# remote_mini.net
KiCad netlist of a schematic drawn in EAGLE
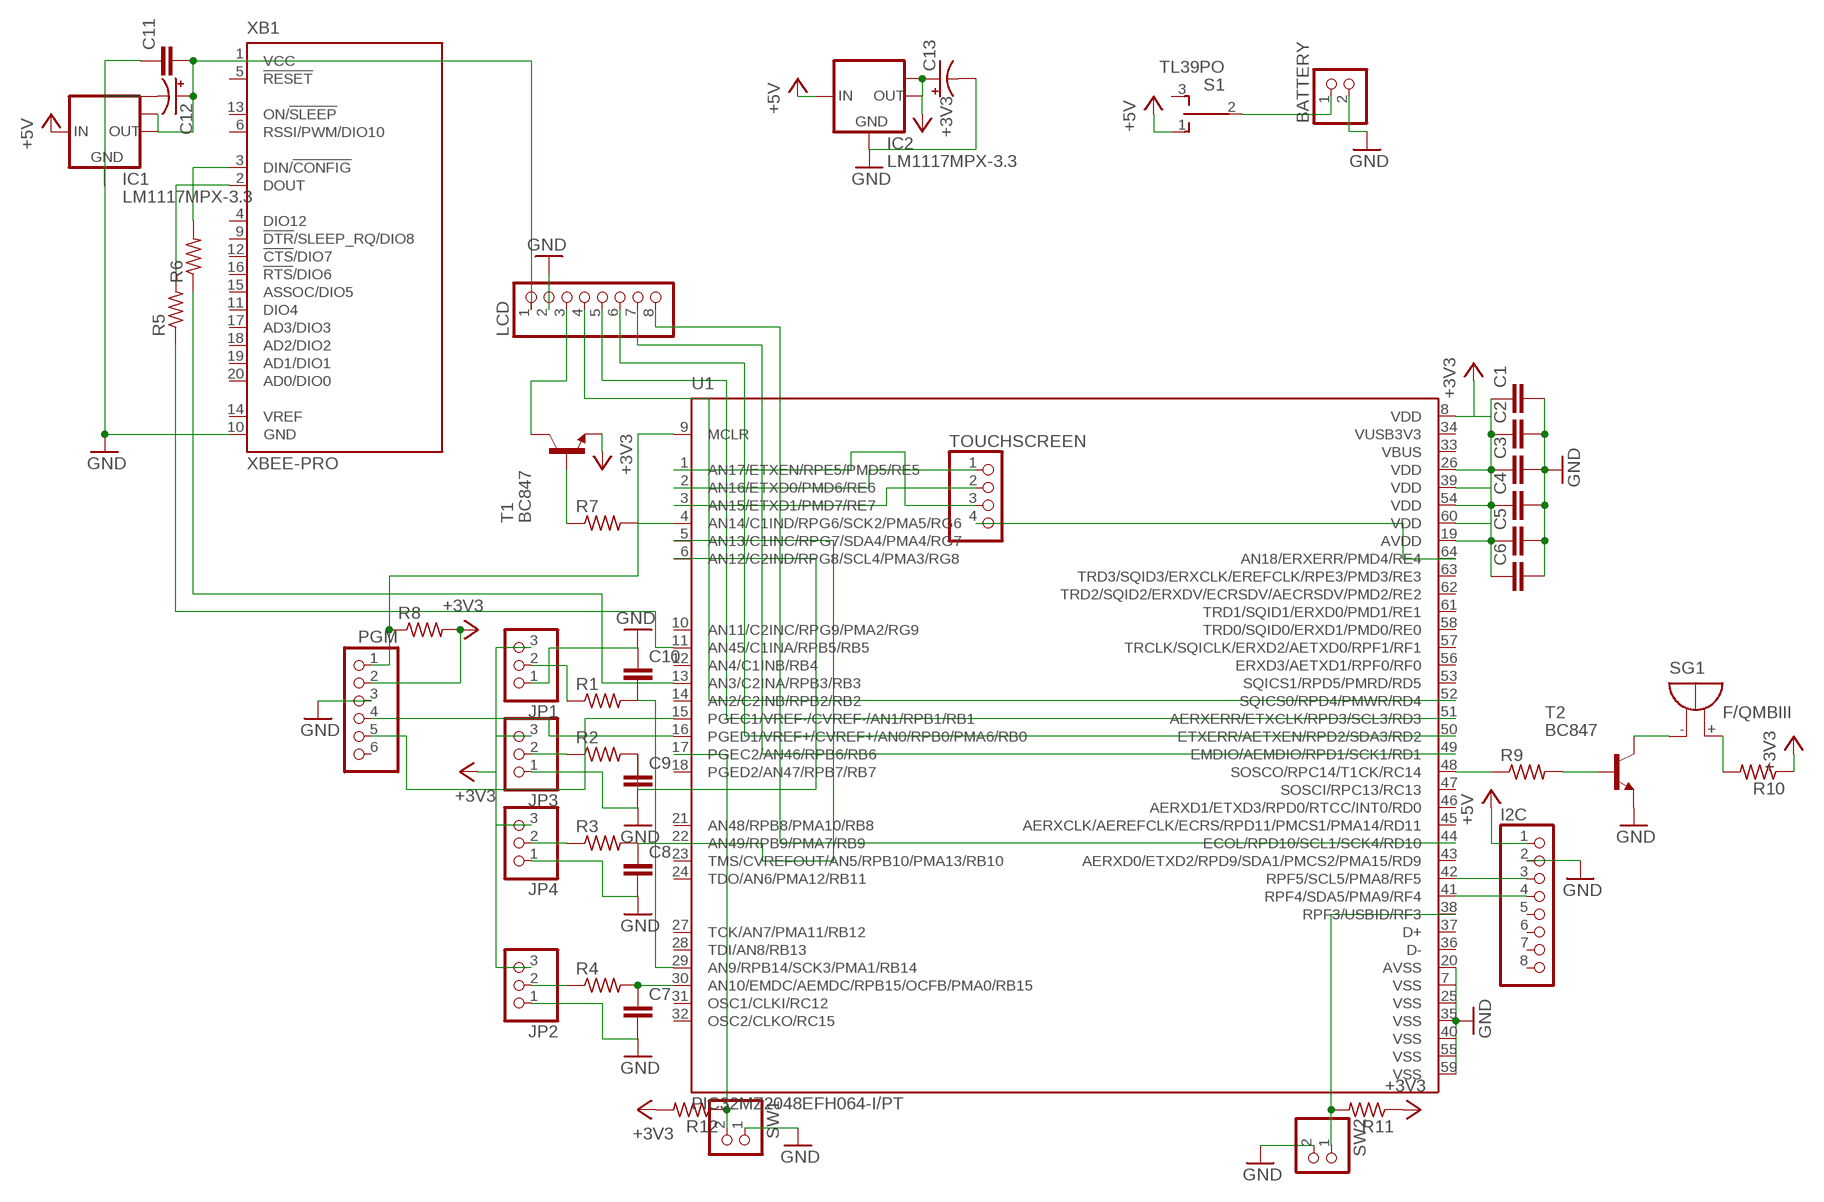
[diagram p0: schematic, sheet 1]

(export (version "E")
  (design (tool "Eeschema 10.0.6"))
  (components
    (comp (ref "BATTERY")
      (value "PINHD-1X2")
      (footprint "eagle-import:1X02")
      (libsource (lib "eagle-import") (part "PINHD-1X2"))
    )
    (comp (ref "C1")
      (value "C-EUC0603")
      (footprint "eagle-import:C0603")
      (libsource (lib "eagle-import") (part "C-EUC0603"))
    )
    (comp (ref "C2")
      (value "C-EUC0603")
      (footprint "eagle-import:C0603")
      (libsource (lib "eagle-import") (part "C-EUC0603"))
    )
    (comp (ref "C3")
      (value "C-EUC0603")
      (footprint "eagle-import:C0603")
      (libsource (lib "eagle-import") (part "C-EUC0603"))
    )
    (comp (ref "C4")
      (value "C-EUC0603")
      (footprint "eagle-import:C0603")
      (libsource (lib "eagle-import") (part "C-EUC0603"))
    )
    (comp (ref "C5")
      (value "C-EUC0603")
      (footprint "eagle-import:C0603")
      (libsource (lib "eagle-import") (part "C-EUC0603"))
    )
    (comp (ref "C6")
      (value "C-EUC0603")
      (footprint "eagle-import:C0603")
      (libsource (lib "eagle-import") (part "C-EUC0603"))
    )
    (comp (ref "C7")
      (value "C-EUC0805")
      (footprint "eagle-import:C0805")
      (libsource (lib "eagle-import") (part "C-EUC0805"))
    )
    (comp (ref "C8")
      (value "C-EUC0805")
      (footprint "eagle-import:C0805")
      (libsource (lib "eagle-import") (part "C-EUC0805"))
    )
    (comp (ref "C9")
      (value "C-EUC0805")
      (footprint "eagle-import:C0805")
      (libsource (lib "eagle-import") (part "C-EUC0805"))
    )
    (comp (ref "C10")
      (value "C-EUC0805")
      (footprint "eagle-import:C0805")
      (libsource (lib "eagle-import") (part "C-EUC0805"))
    )
    (comp (ref "C11")
      (value "C-EUC0603")
      (footprint "eagle-import:C0603")
      (libsource (lib "eagle-import") (part "C-EUC0603"))
    )
    (comp (ref "C12")
      (value "CPOL-USCT7343")
      (footprint "eagle-import:CT7343")
      (libsource (lib "eagle-import") (part "CPOL-USCT7343"))
    )
    (comp (ref "C13")
      (value "CPOL-USCT7343")
      (footprint "eagle-import:CT7343")
      (libsource (lib "eagle-import") (part "CPOL-USCT7343"))
    )
    (comp (ref "I2C")
      (value "PINHD-1X8")
      (footprint "eagle-import:1X08")
      (libsource (lib "eagle-import") (part "PINHD-1X8"))
    )
    (comp (ref "IC1")
      (value "LM1117MPX-3.3")
      (footprint "eagle-import:SOT223")
      (libsource (lib "eagle-import") (part "LM1117MPX-3.3"))
    )
    (comp (ref "IC2")
      (value "LM1117MPX-3.3")
      (footprint "eagle-import:SOT223")
      (libsource (lib "eagle-import") (part "LM1117MPX-3.3"))
    )
    (comp (ref "JP1")
      (value "PINHD-1X3")
      (footprint "eagle-import:1X03")
      (libsource (lib "eagle-import") (part "PINHD-1X3"))
    )
    (comp (ref "JP2")
      (value "PINHD-1X3")
      (footprint "eagle-import:1X03")
      (libsource (lib "eagle-import") (part "PINHD-1X3"))
    )
    (comp (ref "JP3")
      (value "PINHD-1X3")
      (footprint "eagle-import:1X03")
      (libsource (lib "eagle-import") (part "PINHD-1X3"))
    )
    (comp (ref "JP4")
      (value "PINHD-1X3")
      (footprint "eagle-import:1X03")
      (libsource (lib "eagle-import") (part "PINHD-1X3"))
    )
    (comp (ref "LCD")
      (value "PINHD-1X8")
      (footprint "eagle-import:1X08")
      (libsource (lib "eagle-import") (part "PINHD-1X8"))
    )
    (comp (ref "PGM")
      (value "PINHD-1X6")
      (footprint "eagle-import:1X06")
      (libsource (lib "eagle-import") (part "PINHD-1X6"))
    )
    (comp (ref "R1")
      (value "R-US_R0603")
      (footprint "eagle-import:R0603")
      (libsource (lib "eagle-import") (part "R-US_R0603"))
    )
    (comp (ref "R2")
      (value "R-US_R0603")
      (footprint "eagle-import:R0603")
      (libsource (lib "eagle-import") (part "R-US_R0603"))
    )
    (comp (ref "R3")
      (value "R-US_R0603")
      (footprint "eagle-import:R0603")
      (libsource (lib "eagle-import") (part "R-US_R0603"))
    )
    (comp (ref "R4")
      (value "R-US_R0603")
      (footprint "eagle-import:R0603")
      (libsource (lib "eagle-import") (part "R-US_R0603"))
    )
    (comp (ref "R5")
      (value "R-US_R0603")
      (footprint "eagle-import:R0603")
      (libsource (lib "eagle-import") (part "R-US_R0603"))
    )
    (comp (ref "R6")
      (value "R-US_R0603")
      (footprint "eagle-import:R0603")
      (libsource (lib "eagle-import") (part "R-US_R0603"))
    )
    (comp (ref "R7")
      (value "R-US_R0603")
      (footprint "eagle-import:R0603")
      (libsource (lib "eagle-import") (part "R-US_R0603"))
    )
    (comp (ref "R8")
      (value "R-US_R0603")
      (footprint "eagle-import:R0603")
      (libsource (lib "eagle-import") (part "R-US_R0603"))
    )
    (comp (ref "R9")
      (value "R-US_R0603")
      (footprint "eagle-import:R0603")
      (libsource (lib "eagle-import") (part "R-US_R0603"))
    )
    (comp (ref "R10")
      (value "R-US_R0603")
      (footprint "eagle-import:R0603")
      (libsource (lib "eagle-import") (part "R-US_R0603"))
    )
    (comp (ref "R11")
      (value "R-US_R0603")
      (footprint "eagle-import:R0603")
      (libsource (lib "eagle-import") (part "R-US_R0603"))
    )
    (comp (ref "R12")
      (value "R-US_R0603")
      (footprint "eagle-import:R0603")
      (libsource (lib "eagle-import") (part "R-US_R0603"))
    )
    (comp (ref "S1")
      (value "TL39PO")
      (footprint "eagle-import:TL3XPO")
      (libsource (lib "eagle-import") (part "TL39PO"))
    )
    (comp (ref "SG1")
      (value "F/QMBIII")
      (footprint "eagle-import:F_QMBIII")
      (libsource (lib "eagle-import") (part "F/QMBIII"))
    )
    (comp (ref "SW1")
      (value "PINHD-1X2")
      (footprint "eagle-import:1X02")
      (libsource (lib "eagle-import") (part "PINHD-1X2"))
    )
    (comp (ref "SW2")
      (value "PINHD-1X2")
      (footprint "eagle-import:1X02")
      (libsource (lib "eagle-import") (part "PINHD-1X2"))
    )
    (comp (ref "T1")
      (value "BC847")
      (footprint "eagle-import:SOT23")
      (libsource (lib "eagle-import") (part "BC847"))
    )
    (comp (ref "T2")
      (value "BC847")
      (footprint "eagle-import:SOT23")
      (libsource (lib "eagle-import") (part "BC847"))
    )
    (comp (ref "TOUCHSCREEN")
      (value "PINHD-1X4")
      (footprint "eagle-import:1X04")
      (libsource (lib "eagle-import") (part "PINHD-1X4"))
    )
    (comp (ref "U1")
      (value "PIC32MZ2048EFH064-I/PT")
      (footprint "eagle-import:QFP50P1200X1200X120-64N")
      (fields (field (name "MF") "Microchip"))
      (libsource (lib "eagle-import") (part "PIC32MZ2048EFH064-I/PT"))
    )
    (comp (ref "XB1")
      (value "XBEE-PRO")
      (footprint "eagle-import:XBEE-PRO")
      (fields (field (name "MPN") "XBP24-AWI-001"))
      (libsource (lib "eagle-import") (part "XBEE-PRO"))
    )
  )
  (nets
    (net (code "1") (name "+3V3") (class "Default")
      (node (ref "C1") (pin "1") (pinfunction "1_1") (pintype "passive"))
      (node (ref "C13") (pin "+") (pinfunction "+_+") (pintype "passive"))
      (node (ref "C2") (pin "1") (pinfunction "1_1") (pintype "passive"))
      (node (ref "C3") (pin "1") (pinfunction "1_1") (pintype "passive"))
      (node (ref "C4") (pin "1") (pinfunction "1_1") (pintype "passive"))
      (node (ref "C5") (pin "1") (pinfunction "1_1") (pintype "passive"))
      (node (ref "C6") (pin "1") (pinfunction "1_1") (pintype "passive"))
      (node (ref "IC2") (pin "2") (pinfunction "OUT_2") (pintype "passive"))
      (node (ref "IC2") (pin "TAB") (pinfunction "OUT1_TAB") (pintype "passive"))
      (node (ref "JP1") (pin "3") (pinfunction "3_3") (pintype "passive"))
      (node (ref "JP2") (pin "3") (pinfunction "3_3") (pintype "passive"))
      (node (ref "JP3") (pin "3") (pinfunction "3_3") (pintype "passive"))
      (node (ref "JP4") (pin "3") (pinfunction "3_3") (pintype "passive"))
      (node (ref "PGM") (pin "2") (pinfunction "2_2") (pintype "passive"))
      (node (ref "R10") (pin "1") (pinfunction "1_1") (pintype "passive"))
      (node (ref "R11") (pin "1") (pinfunction "1_1") (pintype "passive"))
      (node (ref "R12") (pin "2") (pinfunction "2_2") (pintype "passive"))
      (node (ref "R8") (pin "2") (pinfunction "2_2") (pintype "passive"))
      (node (ref "T1") (pin "2") (pinfunction "E_2") (pintype "passive"))
      (node (ref "U1") (pin "19") (pinfunction "AVDD_19") (pintype "power_in"))
      (node (ref "U1") (pin "26") (pinfunction "VDD_26") (pintype "power_in"))
      (node (ref "U1") (pin "39") (pinfunction "VDD_39") (pintype "power_in"))
      (node (ref "U1") (pin "54") (pinfunction "VDD_54") (pintype "power_in"))
      (node (ref "U1") (pin "60") (pinfunction "VDD_60") (pintype "power_in"))
      (node (ref "U1") (pin "8") (pinfunction "VDD_8") (pintype "power_in"))
    )
    (net (code "2") (name "+5V") (class "Default")
      (node (ref "I2C") (pin "1") (pinfunction "1_1") (pintype "passive"))
      (node (ref "IC1") (pin "3") (pinfunction "IN_3") (pintype "input"))
      (node (ref "IC2") (pin "3") (pinfunction "IN_3") (pintype "input"))
      (node (ref "S1") (pin "1") (pinfunction "O_1") (pintype "passive"))
    )
    (net (code "3") (name "/VBUS") (class "Default")
      (node (ref "U1") (pin "33") (pinfunction "VBUS_33") (pintype "power_in"))
    )
    (net (code "4") (name "/VUSB3V3") (class "Default")
      (node (ref "U1") (pin "34") (pinfunction "VUSB3V3_34") (pintype "power_in"))
    )
    (net (code "5") (name "GND") (class "Default")
      (node (ref "BATTERY") (pin "2") (pinfunction "2_2") (pintype "passive"))
      (node (ref "C1") (pin "2") (pinfunction "2_2") (pintype "passive"))
      (node (ref "C10") (pin "1") (pinfunction "1_1") (pintype "passive"))
      (node (ref "C11") (pin "1") (pinfunction "1_1") (pintype "passive"))
      (node (ref "C12") (pin "-") (pinfunction "-_-") (pintype "passive"))
      (node (ref "C13") (pin "-") (pinfunction "-_-") (pintype "passive"))
      (node (ref "C2") (pin "2") (pinfunction "2_2") (pintype "passive"))
      (node (ref "C3") (pin "2") (pinfunction "2_2") (pintype "passive"))
      (node (ref "C4") (pin "2") (pinfunction "2_2") (pintype "passive"))
      (node (ref "C5") (pin "2") (pinfunction "2_2") (pintype "passive"))
      (node (ref "C6") (pin "2") (pinfunction "2_2") (pintype "passive"))
      (node (ref "C7") (pin "2") (pinfunction "2_2") (pintype "passive"))
      (node (ref "C8") (pin "2") (pinfunction "2_2") (pintype "passive"))
      (node (ref "C9") (pin "2") (pinfunction "2_2") (pintype "passive"))
      (node (ref "I2C") (pin "2") (pinfunction "2_2") (pintype "passive"))
      (node (ref "IC1") (pin "1") (pinfunction "GND_1") (pintype "input"))
      (node (ref "IC2") (pin "1") (pinfunction "GND_1") (pintype "input"))
      (node (ref "JP1") (pin "1") (pinfunction "1_1") (pintype "passive"))
      (node (ref "JP2") (pin "1") (pinfunction "1_1") (pintype "passive"))
      (node (ref "JP3") (pin "1") (pinfunction "1_1") (pintype "passive"))
      (node (ref "JP4") (pin "1") (pinfunction "1_1") (pintype "passive"))
      (node (ref "LCD") (pin "2") (pinfunction "2_2") (pintype "passive"))
      (node (ref "PGM") (pin "3") (pinfunction "3_3") (pintype "passive"))
      (node (ref "SW1") (pin "1") (pinfunction "1_1") (pintype "passive"))
      (node (ref "SW2") (pin "2") (pinfunction "2_2") (pintype "passive"))
      (node (ref "T2") (pin "2") (pinfunction "E_2") (pintype "passive"))
      (node (ref "U1") (pin "20") (pinfunction "AVSS_20") (pintype "power_in"))
      (node (ref "U1") (pin "25") (pinfunction "VSS_25") (pintype "power_in"))
      (node (ref "U1") (pin "35") (pinfunction "VSS_35") (pintype "power_in"))
      (node (ref "U1") (pin "40") (pinfunction "VSS_40") (pintype "power_in"))
      (node (ref "U1") (pin "55") (pinfunction "VSS_55") (pintype "power_in"))
      (node (ref "U1") (pin "59") (pinfunction "VSS_59") (pintype "power_in"))
      (node (ref "U1") (pin "7") (pinfunction "VSS_7") (pintype "power_in"))
      (node (ref "XB1") (pin "10") (pinfunction "GND_10") (pintype "power_in"))
    )
    (net (code "6") (name "Net-(IC1-OUT)") (class "Default")
      (node (ref "C11") (pin "2") (pinfunction "2_2") (pintype "passive"))
      (node (ref "C12") (pin "+") (pinfunction "+_+") (pintype "passive"))
      (node (ref "IC1") (pin "2") (pinfunction "OUT_2") (pintype "passive"))
      (node (ref "IC1") (pin "TAB") (pinfunction "OUT1_TAB") (pintype "passive"))
      (node (ref "LCD") (pin "1") (pinfunction "1_1") (pintype "passive"))
      (node (ref "XB1") (pin "1") (pinfunction "VCC_1") (pintype "power_in"))
    )
    (net (code "7") (name "Net-(JP1-Pad2)") (class "Default")
      (node (ref "JP1") (pin "2") (pinfunction "2_2") (pintype "passive"))
      (node (ref "R1") (pin "1") (pinfunction "1_1") (pintype "passive"))
    )
    (net (code "8") (name "Net-(JP2-Pad2)") (class "Default")
      (node (ref "JP2") (pin "2") (pinfunction "2_2") (pintype "passive"))
      (node (ref "R4") (pin "1") (pinfunction "1_1") (pintype "passive"))
    )
    (net (code "9") (name "Net-(JP3-Pad2)") (class "Default")
      (node (ref "JP3") (pin "2") (pinfunction "2_2") (pintype "passive"))
      (node (ref "R2") (pin "1") (pinfunction "1_1") (pintype "passive"))
    )
    (net (code "10") (name "Net-(JP4-Pad2)") (class "Default")
      (node (ref "JP4") (pin "2") (pinfunction "2_2") (pintype "passive"))
      (node (ref "R3") (pin "1") (pinfunction "1_1") (pintype "passive"))
    )
    (net (code "11") (name "Net-(S1-P)") (class "Default")
      (node (ref "BATTERY") (pin "1") (pinfunction "1_1") (pintype "passive"))
      (node (ref "S1") (pin "2") (pinfunction "P_2") (pintype "passive"))
    )
    (net (code "12") (name "Net-(SG1-+)") (class "Default")
      (node (ref "SG1") (pin "-") (pinfunction "+_-") (pintype "passive"))
      (node (ref "T2") (pin "3") (pinfunction "C_3") (pintype "passive"))
    )
    (net (code "13") (name "Net-(SG1--)") (class "Default")
      (node (ref "R10") (pin "2") (pinfunction "2_2") (pintype "passive"))
      (node (ref "SG1") (pin "+") (pinfunction "-_+") (pintype "passive"))
    )
    (net (code "14") (name "Net-(T1-B)") (class "Default")
      (node (ref "R7") (pin "1") (pinfunction "1_1") (pintype "passive"))
      (node (ref "T1") (pin "1") (pinfunction "B_1") (pintype "passive"))
    )
    (net (code "15") (name "Net-(T1-C)") (class "Default")
      (node (ref "LCD") (pin "3") (pinfunction "3_3") (pintype "passive"))
      (node (ref "T1") (pin "3") (pinfunction "C_3") (pintype "passive"))
    )
    (net (code "16") (name "Net-(T2-B)") (class "Default")
      (node (ref "R9") (pin "2") (pinfunction "2_2") (pintype "passive"))
      (node (ref "T2") (pin "1") (pinfunction "B_1") (pintype "passive"))
    )
    (net (code "17") (name "Net-(U1-AERXERR{slash}ETXCLK{slash}RPD3{slash}SCL3{slash}RD3)") (class "Default")
      (node (ref "LCD") (pin "5") (pinfunction "5_5") (pintype "passive"))
      (node (ref "U1") (pin "51") (pinfunction "AERXERR/ETXCLK/RPD3/SCL3/RD3_51") (pintype "bidirectional"))
    )
    (net (code "18") (name "Net-(U1-AN3{slash}C2INA{slash}RPB3{slash}RB3)") (class "Default")
      (node (ref "R6") (pin "1") (pinfunction "1_1") (pintype "passive"))
      (node (ref "U1") (pin "13") (pinfunction "AN3/C2INA/RPB3/RB3_13") (pintype "bidirectional"))
    )
    (net (code "19") (name "Net-(U1-AN9{slash}RPB14{slash}SCK3{slash}PMA1{slash}RB14)") (class "Default")
      (node (ref "C10") (pin "2") (pinfunction "2_2") (pintype "passive"))
      (node (ref "R1") (pin "2") (pinfunction "2_2") (pintype "passive"))
      (node (ref "U1") (pin "29") (pinfunction "AN9/RPB14/SCK3/PMA1/RB14_29") (pintype "bidirectional"))
    )
    (net (code "20") (name "Net-(U1-AN10{slash}EMDC{slash}AEMDC{slash}RPB15{slash}OCFB{slash}PMA0{slash}RB15)") (class "Default")
      (node (ref "C7") (pin "1") (pinfunction "1_1") (pintype "passive"))
      (node (ref "R4") (pin "2") (pinfunction "2_2") (pintype "passive"))
      (node (ref "U1") (pin "30") (pinfunction "AN10/EMDC/AEMDC/RPB15/OCFB/PMA0/RB15_30") (pintype "bidirectional"))
    )
    (net (code "21") (name "Net-(U1-AN12{slash}C2IND{slash}RPG8{slash}SCL4{slash}PMA3{slash}RG8)") (class "Default")
      (node (ref "C9") (pin "1") (pinfunction "1_1") (pintype "passive"))
      (node (ref "R2") (pin "2") (pinfunction "2_2") (pintype "passive"))
      (node (ref "U1") (pin "6") (pinfunction "AN12/C2IND/RPG8/SCL4/PMA3/RG8_6") (pintype "bidirectional"))
    )
    (net (code "22") (name "Net-(U1-AN13{slash}C1INC{slash}RPG7{slash}SDA4{slash}PMA4{slash}RG7)") (class "Default")
      (node (ref "C8") (pin "1") (pinfunction "1_1") (pintype "passive"))
      (node (ref "R3") (pin "2") (pinfunction "2_2") (pintype "passive"))
      (node (ref "U1") (pin "5") (pinfunction "AN13/C1INC/RPG7/SDA4/PMA4/RG7_5") (pintype "bidirectional"))
    )
    (net (code "23") (name "Net-(U1-AN14{slash}C1IND{slash}RPG6{slash}SCK2{slash}PMA5{slash}RG6)") (class "Default")
      (node (ref "R7") (pin "2") (pinfunction "2_2") (pintype "passive"))
      (node (ref "U1") (pin "4") (pinfunction "AN14/C1IND/RPG6/SCK2/PMA5/RG6_4") (pintype "bidirectional"))
    )
    (net (code "24") (name "Net-(U1-AN15{slash}ETXD1{slash}PMD7{slash}RE7)") (class "Default")
      (node (ref "TOUCHSCREEN") (pin "2") (pinfunction "2_2") (pintype "passive"))
      (node (ref "U1") (pin "3") (pinfunction "AN15/ETXD1/PMD7/RE7_3") (pintype "bidirectional"))
    )
    (net (code "25") (name "Net-(U1-AN16{slash}ETXD0{slash}PMD6{slash}RE6)") (class "Default")
      (node (ref "TOUCHSCREEN") (pin "1") (pinfunction "1_1") (pintype "passive"))
      (node (ref "U1") (pin "2") (pinfunction "AN16/ETXD0/PMD6/RE6_2") (pintype "bidirectional"))
    )
    (net (code "26") (name "Net-(U1-AN17{slash}ETXEN{slash}RPE5{slash}PMD5{slash}RE5)") (class "Default")
      (node (ref "TOUCHSCREEN") (pin "3") (pinfunction "3_3") (pintype "passive"))
      (node (ref "U1") (pin "1") (pinfunction "AN17/ETXEN/RPE5/PMD5/RE5_1") (pintype "bidirectional"))
    )
    (net (code "27") (name "Net-(U1-AN18{slash}ERXERR{slash}PMD4{slash}RE4)") (class "Default")
      (node (ref "TOUCHSCREEN") (pin "4") (pinfunction "4_4") (pintype "passive"))
      (node (ref "U1") (pin "64") (pinfunction "AN18/ERXERR/PMD4/RE4_64") (pintype "bidirectional"))
    )
    (net (code "28") (name "Net-(U1-AN45{slash}C1INA{slash}RPB5{slash}RB5)") (class "Default")
      (node (ref "R5") (pin "1") (pinfunction "1_1") (pintype "passive"))
      (node (ref "U1") (pin "11") (pinfunction "AN45/C1INA/RPB5/RB5_11") (pintype "bidirectional"))
    )
    (net (code "29") (name "Net-(U1-ECOL{slash}RPD10{slash}SCL1{slash}SCK4{slash}RD10)") (class "Default")
      (node (ref "LCD") (pin "8") (pinfunction "8_8") (pintype "passive"))
      (node (ref "U1") (pin "44") (pinfunction "ECOL/RPD10/SCL1/SCK4/RD10_44") (pintype "bidirectional"))
    )
    (net (code "30") (name "Net-(U1-EMDIO{slash}AEMDIO{slash}RPD1{slash}SCK1{slash}RD1)") (class "Default")
      (node (ref "LCD") (pin "7") (pinfunction "7_7") (pintype "passive"))
      (node (ref "U1") (pin "49") (pinfunction "EMDIO/AEMDIO/RPD1/SCK1/RD1_49") (pintype "bidirectional"))
    )
    (net (code "31") (name "Net-(U1-ETXERR{slash}AETXEN{slash}RPD2{slash}SDA3{slash}RD2)") (class "Default")
      (node (ref "LCD") (pin "6") (pinfunction "6_6") (pintype "passive"))
      (node (ref "U1") (pin "50") (pinfunction "ETXERR/AETXEN/RPD2/SDA3/RD2_50") (pintype "bidirectional"))
    )
    (net (code "32") (name "Net-(U1-MCLR)") (class "Default")
      (node (ref "PGM") (pin "1") (pinfunction "1_1") (pintype "passive"))
      (node (ref "R8") (pin "1") (pinfunction "1_1") (pintype "passive"))
      (node (ref "U1") (pin "9") (pinfunction "MCLR_9") (pintype "input"))
    )
    (net (code "33") (name "Net-(U1-PGEC1{slash}VREF-{slash}CVREF-{slash}AN1{slash}RPB1{slash}RB1)") (class "Default")
      (node (ref "PGM") (pin "5") (pinfunction "5_5") (pintype "passive"))
      (node (ref "U1") (pin "15") (pinfunction "PGEC1/VREF-/CVREF-/AN1/RPB1/RB1_15") (pintype "bidirectional"))
    )
    (net (code "34") (name "Net-(U1-PGEC2{slash}AN46{slash}RPB6{slash}RB6)") (class "Default")
      (node (ref "R12") (pin "1") (pinfunction "1_1") (pintype "passive"))
      (node (ref "SW1") (pin "2") (pinfunction "2_2") (pintype "passive"))
      (node (ref "U1") (pin "17") (pinfunction "PGEC2/AN46/RPB6/RB6_17") (pintype "bidirectional"))
    )
    (net (code "35") (name "Net-(U1-PGED1{slash}VREF+{slash}CVREF+{slash}AN0{slash}RPB0{slash}PMA6{slash}RB0)") (class "Default")
      (node (ref "PGM") (pin "4") (pinfunction "4_4") (pintype "passive"))
      (node (ref "U1") (pin "16") (pinfunction "PGED1/VREF+/CVREF+/AN0/RPB0/PMA6/RB0_16") (pintype "bidirectional"))
    )
    (net (code "36") (name "Net-(U1-RPF3{slash}USBID{slash}RF3)") (class "Default")
      (node (ref "R11") (pin "2") (pinfunction "2_2") (pintype "passive"))
      (node (ref "SW2") (pin "1") (pinfunction "1_1") (pintype "passive"))
      (node (ref "U1") (pin "38") (pinfunction "RPF3/USBID/RF3_38") (pintype "bidirectional"))
    )
    (net (code "37") (name "Net-(U1-RPF4{slash}SDA5{slash}PMA9{slash}RF4)") (class "Default")
      (node (ref "I2C") (pin "4") (pinfunction "4_4") (pintype "passive"))
      (node (ref "U1") (pin "41") (pinfunction "RPF4/SDA5/PMA9/RF4_41") (pintype "bidirectional"))
    )
    (net (code "38") (name "Net-(U1-RPF5{slash}SCL5{slash}PMA8{slash}RF5)") (class "Default")
      (node (ref "I2C") (pin "3") (pinfunction "3_3") (pintype "passive"))
      (node (ref "U1") (pin "42") (pinfunction "RPF5/SCL5/PMA8/RF5_42") (pintype "bidirectional"))
    )
    (net (code "39") (name "Net-(U1-SOSCO{slash}RPC14{slash}T1CK{slash}RC14)") (class "Default")
      (node (ref "R9") (pin "1") (pinfunction "1_1") (pintype "passive"))
      (node (ref "U1") (pin "48") (pinfunction "SOSCO/RPC14/T1CK/RC14_48") (pintype "bidirectional"))
    )
    (net (code "40") (name "Net-(U1-SQICS0{slash}RPD4{slash}PMWR{slash}RD4)") (class "Default")
      (node (ref "LCD") (pin "4") (pinfunction "4_4") (pintype "passive"))
      (node (ref "U1") (pin "52") (pinfunction "SQICS0/RPD4/PMWR/RD4_52") (pintype "bidirectional"))
    )
    (net (code "41") (name "Net-(XB1-DIN{slash}~{CONFIG})") (class "Default")
      (node (ref "R6") (pin "2") (pinfunction "2_2") (pintype "passive"))
      (node (ref "XB1") (pin "3") (pinfunction "DIN/~{CONFIG}_3") (pintype "input"))
    )
    (net (code "42") (name "Net-(XB1-DOUT)") (class "Default")
      (node (ref "R5") (pin "2") (pinfunction "2_2") (pintype "passive"))
      (node (ref "XB1") (pin "2") (pinfunction "DOUT_2") (pintype "output"))
    )
    (net (code "43") (name "unconnected-(I2C-Pad5)") (class "Default")
      (node (ref "I2C") (pin "5") (pinfunction "5_5") (pintype "passive"))
    )
    (net (code "44") (name "unconnected-(I2C-Pad6)") (class "Default")
      (node (ref "I2C") (pin "6") (pinfunction "6_6") (pintype "passive"))
    )
    (net (code "45") (name "unconnected-(I2C-Pad7)") (class "Default")
      (node (ref "I2C") (pin "7") (pinfunction "7_7") (pintype "passive"))
    )
    (net (code "46") (name "unconnected-(I2C-Pad8)") (class "Default")
      (node (ref "I2C") (pin "8") (pinfunction "8_8") (pintype "passive"))
    )
    (net (code "47") (name "unconnected-(PGM-Pad6)") (class "Default")
      (node (ref "PGM") (pin "6") (pinfunction "6_6") (pintype "passive"))
    )
    (net (code "48") (name "unconnected-(S1-S-Pad3)") (class "Default")
      (node (ref "S1") (pin "3") (pinfunction "S_3") (pintype "passive"))
    )
    (net (code "49") (name "unconnected-(U1-AERXCLK{slash}AEREFCLK{slash}ECRS{slash}RPD11{slash}PMCS1{slash}PMA14{slash}RD11-Pad45)") (class "Default")
      (node (ref "U1") (pin "45") (pinfunction "AERXCLK/AEREFCLK/ECRS/RPD11/PMCS1/PMA14/RD11_45") (pintype "bidirectional"))
    )
    (net (code "50") (name "unconnected-(U1-AERXD0{slash}ETXD2{slash}RPD9{slash}SDA1{slash}PMCS2{slash}PMA15{slash}RD9-Pad43)") (class "Default")
      (node (ref "U1") (pin "43") (pinfunction "AERXD0/ETXD2/RPD9/SDA1/PMCS2/PMA15/RD9_43") (pintype "bidirectional"))
    )
    (net (code "51") (name "unconnected-(U1-AERXD1{slash}ETXD3{slash}RPD0{slash}RTCC{slash}INT0{slash}RD0-Pad46)") (class "Default")
      (node (ref "U1") (pin "46") (pinfunction "AERXD1/ETXD3/RPD0/RTCC/INT0/RD0_46") (pintype "bidirectional"))
    )
    (net (code "52") (name "unconnected-(U1-AN2{slash}C2INB{slash}RPB2{slash}RB2-Pad14)") (class "Default")
      (node (ref "U1") (pin "14") (pinfunction "AN2/C2INB/RPB2/RB2_14") (pintype "bidirectional"))
    )
    (net (code "53") (name "unconnected-(U1-AN4{slash}C1INB{slash}RB4-Pad12)") (class "Default")
      (node (ref "U1") (pin "12") (pinfunction "AN4/C1INB/RB4_12") (pintype "bidirectional"))
    )
    (net (code "54") (name "unconnected-(U1-AN11{slash}C2INC{slash}RPG9{slash}PMA2{slash}RG9-Pad10)") (class "Default")
      (node (ref "U1") (pin "10") (pinfunction "AN11/C2INC/RPG9/PMA2/RG9_10") (pintype "bidirectional"))
    )
    (net (code "55") (name "unconnected-(U1-AN48{slash}RPB8{slash}PMA10{slash}RB8-Pad21)") (class "Default")
      (node (ref "U1") (pin "21") (pinfunction "AN48/RPB8/PMA10/RB8_21") (pintype "bidirectional"))
    )
    (net (code "56") (name "unconnected-(U1-AN49{slash}RPB9{slash}PMA7{slash}RB9-Pad22)") (class "Default")
      (node (ref "U1") (pin "22") (pinfunction "AN49/RPB9/PMA7/RB9_22") (pintype "bidirectional"))
    )
    (net (code "57") (name "unconnected-(U1-D+-Pad37)") (class "Default")
      (node (ref "U1") (pin "37") (pinfunction "D+_37") (pintype "bidirectional"))
    )
    (net (code "58") (name "unconnected-(U1-D--Pad36)") (class "Default")
      (node (ref "U1") (pin "36") (pinfunction "D-_36") (pintype "bidirectional"))
    )
    (net (code "59") (name "unconnected-(U1-ERXD3{slash}AETXD1{slash}RPF0{slash}RF0-Pad56)") (class "Default")
      (node (ref "U1") (pin "56") (pinfunction "ERXD3/AETXD1/RPF0/RF0_56") (pintype "bidirectional"))
    )
    (net (code "60") (name "unconnected-(U1-OSC1{slash}CLKI{slash}RC12-Pad31)") (class "Default")
      (node (ref "U1") (pin "31") (pinfunction "OSC1/CLKI/RC12_31") (pintype "bidirectional"))
    )
    (net (code "61") (name "unconnected-(U1-OSC2{slash}CLKO{slash}RC15-Pad32)") (class "Default")
      (node (ref "U1") (pin "32") (pinfunction "OSC2/CLKO/RC15_32") (pintype "bidirectional"))
    )
    (net (code "62") (name "unconnected-(U1-PGED2{slash}AN47{slash}RPB7{slash}RB7-Pad18)") (class "Default")
      (node (ref "U1") (pin "18") (pinfunction "PGED2/AN47/RPB7/RB7_18") (pintype "bidirectional"))
    )
    (net (code "63") (name "unconnected-(U1-SOSCI{slash}RPC13{slash}RC13-Pad47)") (class "Default")
      (node (ref "U1") (pin "47") (pinfunction "SOSCI/RPC13/RC13_47") (pintype "bidirectional"))
    )
    (net (code "64") (name "unconnected-(U1-SQICS1{slash}RPD5{slash}PMRD{slash}RD5-Pad53)") (class "Default")
      (node (ref "U1") (pin "53") (pinfunction "SQICS1/RPD5/PMRD/RD5_53") (pintype "bidirectional"))
    )
    (net (code "65") (name "unconnected-(U1-TCK{slash}AN7{slash}PMA11{slash}RB12-Pad27)") (class "Default")
      (node (ref "U1") (pin "27") (pinfunction "TCK/AN7/PMA11/RB12_27") (pintype "bidirectional"))
    )
    (net (code "66") (name "unconnected-(U1-TDI{slash}AN8{slash}RB13-Pad28)") (class "Default")
      (node (ref "U1") (pin "28") (pinfunction "TDI/AN8/RB13_28") (pintype "bidirectional"))
    )
    (net (code "67") (name "unconnected-(U1-TDO{slash}AN6{slash}PMA12{slash}RB11-Pad24)") (class "Default")
      (node (ref "U1") (pin "24") (pinfunction "TDO/AN6/PMA12/RB11_24") (pintype "bidirectional"))
    )
    (net (code "68") (name "unconnected-(U1-TMS{slash}CVREFOUT{slash}AN5{slash}RPB10{slash}PMA13{slash}RB10-Pad23)") (class "Default")
      (node (ref "U1") (pin "23") (pinfunction "TMS/CVREFOUT/AN5/RPB10/PMA13/RB10_23") (pintype "bidirectional"))
    )
    (net (code "69") (name "unconnected-(U1-TRCLK{slash}SQICLK{slash}ERXD2{slash}AETXD0{slash}RPF1{slash}RF1-Pad57)") (class "Default")
      (node (ref "U1") (pin "57") (pinfunction "TRCLK/SQICLK/ERXD2/AETXD0/RPF1/RF1_57") (pintype "bidirectional"))
    )
    (net (code "70") (name "unconnected-(U1-TRD0{slash}SQID0{slash}ERXD1{slash}PMD0{slash}RE0-Pad58)") (class "Default")
      (node (ref "U1") (pin "58") (pinfunction "TRD0/SQID0/ERXD1/PMD0/RE0_58") (pintype "bidirectional"))
    )
    (net (code "71") (name "unconnected-(U1-TRD1{slash}SQID1{slash}ERXD0{slash}PMD1{slash}RE1-Pad61)") (class "Default")
      (node (ref "U1") (pin "61") (pinfunction "TRD1/SQID1/ERXD0/PMD1/RE1_61") (pintype "bidirectional"))
    )
    (net (code "72") (name "unconnected-(U1-TRD2{slash}SQID2{slash}ERXDV{slash}ECRSDV{slash}AECRSDV{slash}PMD2{slash}RE2-Pad62)") (class "Default")
      (node (ref "U1") (pin "62") (pinfunction "TRD2/SQID2/ERXDV/ECRSDV/AECRSDV/PMD2/RE2_62") (pintype "bidirectional"))
    )
    (net (code "73") (name "unconnected-(U1-TRD3{slash}SQID3{slash}ERXCLK{slash}EREFCLK{slash}RPE3{slash}PMD3{slash}RE3-Pad63)") (class "Default")
      (node (ref "U1") (pin "63") (pinfunction "TRD3/SQID3/ERXCLK/EREFCLK/RPE3/PMD3/RE3_63") (pintype "bidirectional"))
    )
    (net (code "74") (name "unconnected-(XB1-AD0{slash}DIO0-Pad20)") (class "Default")
      (node (ref "XB1") (pin "20") (pinfunction "AD0/DIO0_20") (pintype "bidirectional"))
    )
    (net (code "75") (name "unconnected-(XB1-AD1{slash}DIO1-Pad19)") (class "Default")
      (node (ref "XB1") (pin "19") (pinfunction "AD1/DIO1_19") (pintype "bidirectional"))
    )
    (net (code "76") (name "unconnected-(XB1-AD2{slash}DIO2-Pad18)") (class "Default")
      (node (ref "XB1") (pin "18") (pinfunction "AD2/DIO2_18") (pintype "bidirectional"))
    )
    (net (code "77") (name "unconnected-(XB1-AD3{slash}DIO3-Pad17)") (class "Default")
      (node (ref "XB1") (pin "17") (pinfunction "AD3/DIO3_17") (pintype "bidirectional"))
    )
    (net (code "78") (name "unconnected-(XB1-ASSOC{slash}DIO5-Pad15)") (class "Default")
      (node (ref "XB1") (pin "15") (pinfunction "ASSOC/DIO5_15") (pintype "bidirectional"))
    )
    (net (code "79") (name "unconnected-(XB1-DIO4-Pad11)") (class "Default")
      (node (ref "XB1") (pin "11") (pinfunction "DIO4_11") (pintype "bidirectional"))
    )
    (net (code "80") (name "unconnected-(XB1-DIO12-Pad4)") (class "Default")
      (node (ref "XB1") (pin "4") (pinfunction "DIO12_4") (pintype "bidirectional"))
    )
    (net (code "81") (name "unconnected-(XB1-ON{slash}~{SLEEP}-Pad13)") (class "Default")
      (node (ref "XB1") (pin "13") (pinfunction "ON/~{SLEEP}_13") (pintype "output"))
    )
    (net (code "82") (name "unconnected-(XB1-RSSI{slash}PWM{slash}DIO10-Pad6)") (class "Default")
      (node (ref "XB1") (pin "6") (pinfunction "RSSI/PWM/DIO10_6") (pintype "output"))
    )
    (net (code "83") (name "unconnected-(XB1-VREF-Pad14)") (class "Default")
      (node (ref "XB1") (pin "14") (pinfunction "VREF_14") (pintype "input"))
    )
    (net (code "84") (name "unconnected-(XB1-~{CTS}{slash}DIO7-Pad12)") (class "Default")
      (node (ref "XB1") (pin "12") (pinfunction "~{CTS}/DIO7_12") (pintype "bidirectional"))
    )
    (net (code "85") (name "unconnected-(XB1-~{DTR}{slash}SLEEP_RQ{slash}DIO8-Pad9)") (class "Default")
      (node (ref "XB1") (pin "9") (pinfunction "~{DTR}/SLEEP_RQ/DIO8_9") (pintype "bidirectional"))
    )
    (net (code "86") (name "unconnected-(XB1-~{RESET}-Pad5)") (class "Default")
      (node (ref "XB1") (pin "5") (pinfunction "~{RESET}_5") (pintype "input"))
    )
    (net (code "87") (name "unconnected-(XB1-~{RTS}{slash}DIO6-Pad16)") (class "Default")
      (node (ref "XB1") (pin "16") (pinfunction "~{RTS}/DIO6_16") (pintype "bidirectional"))
    )
  )
)
